# P08R6.net
KiCad netlist of a schematic drawn in EAGLE
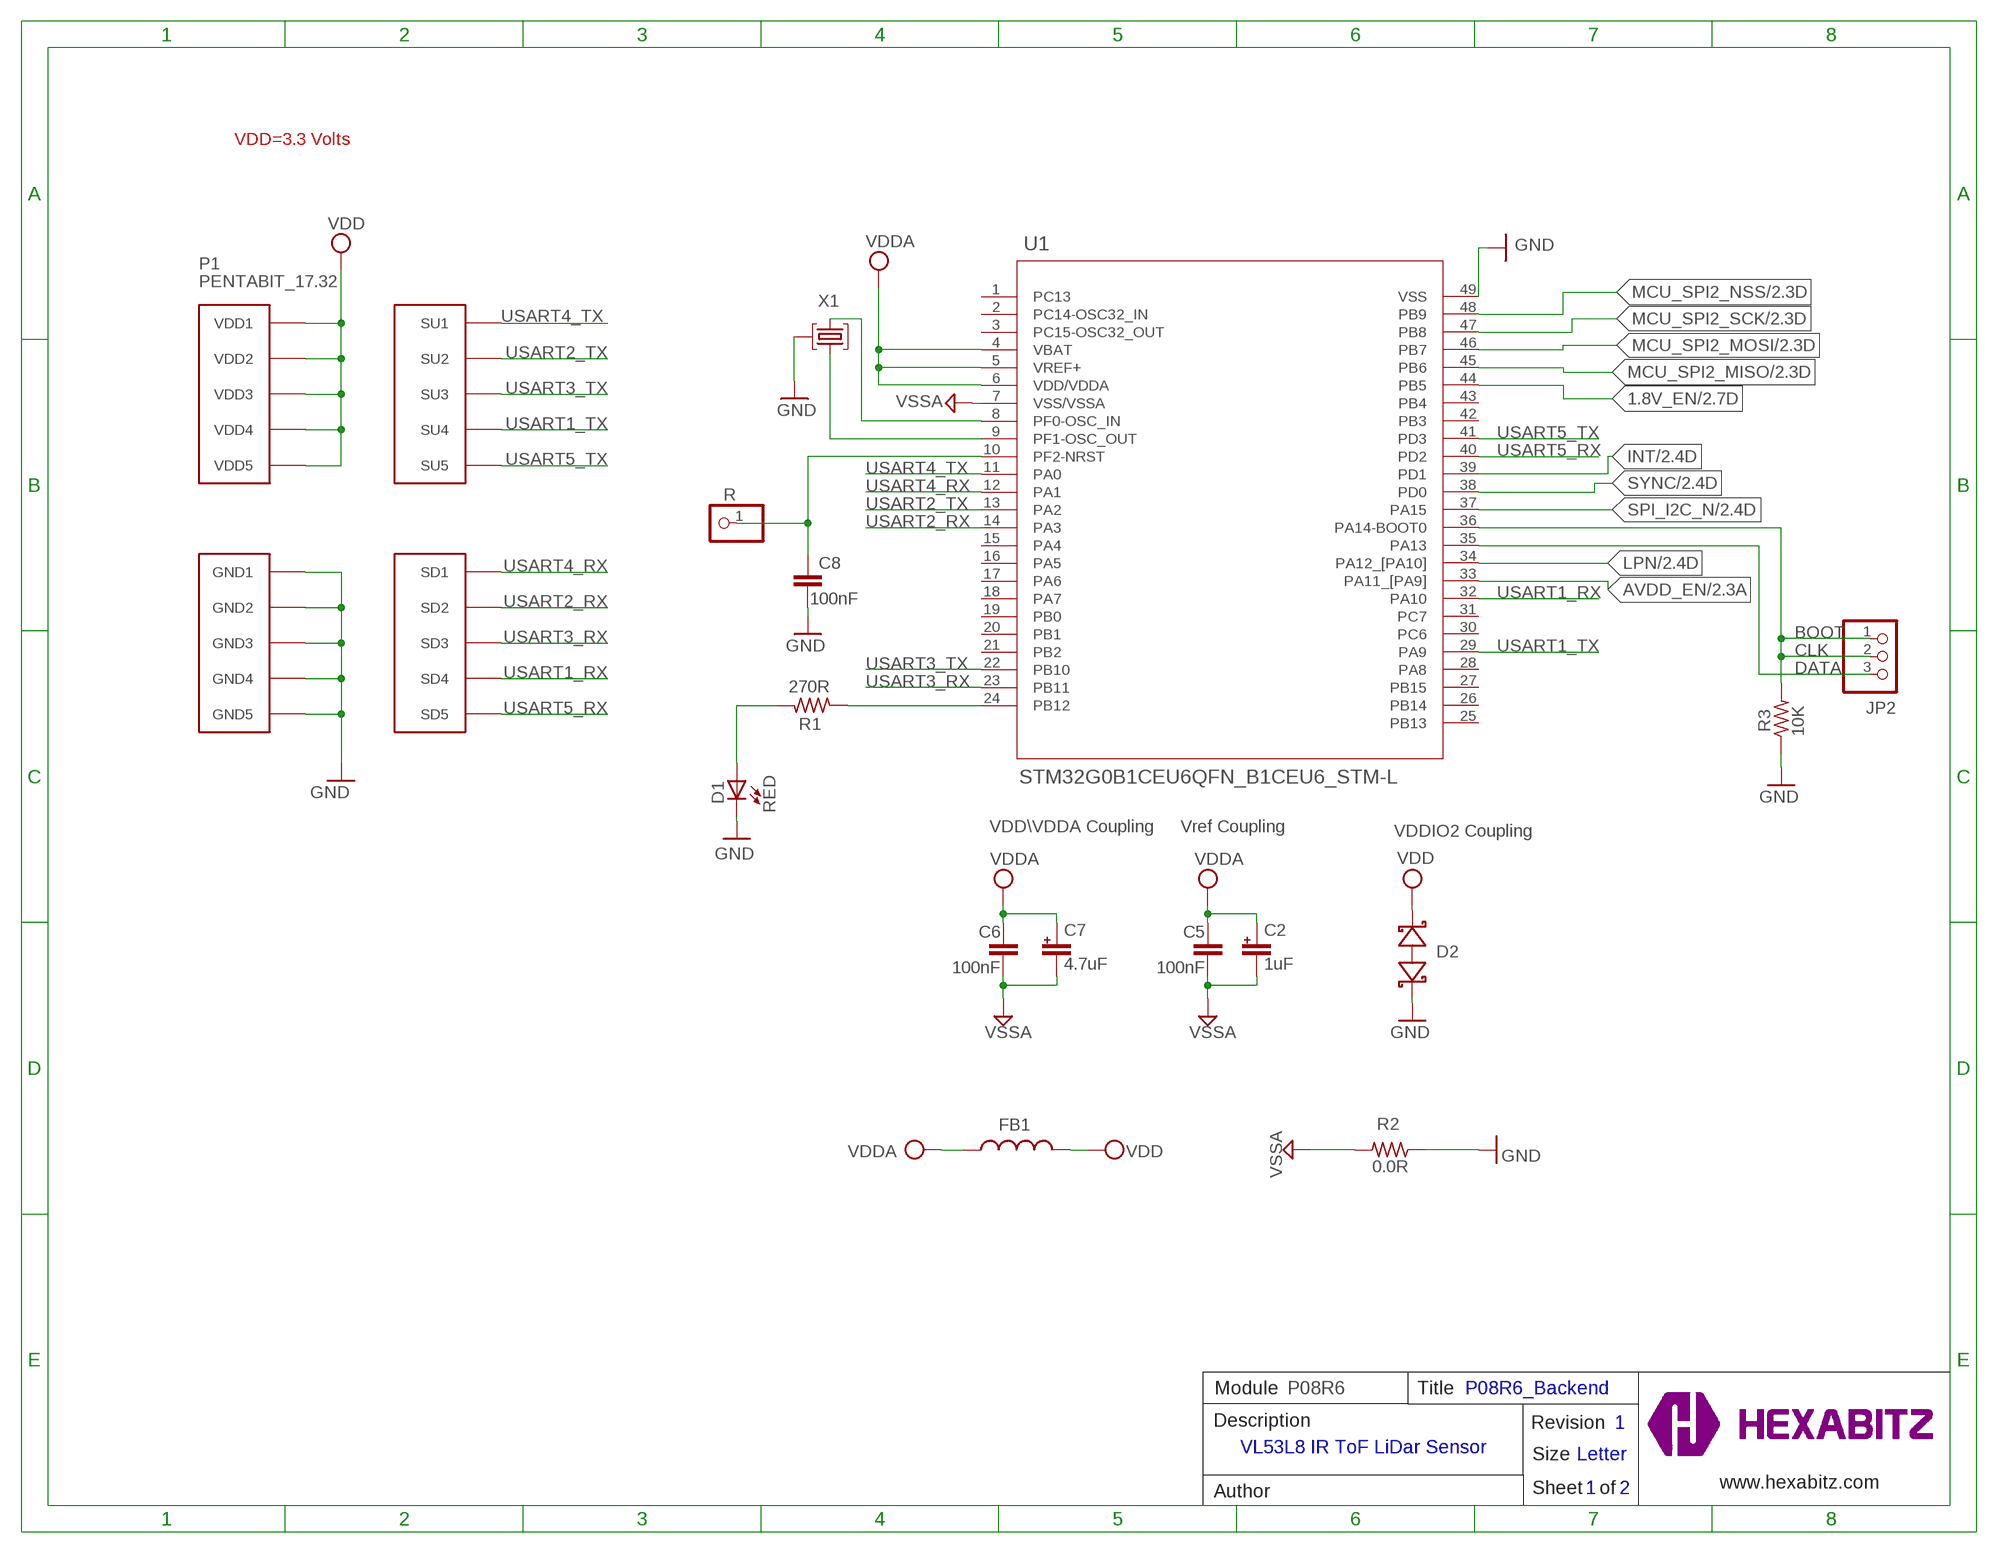
[diagram p0: schematic, sheet 1]
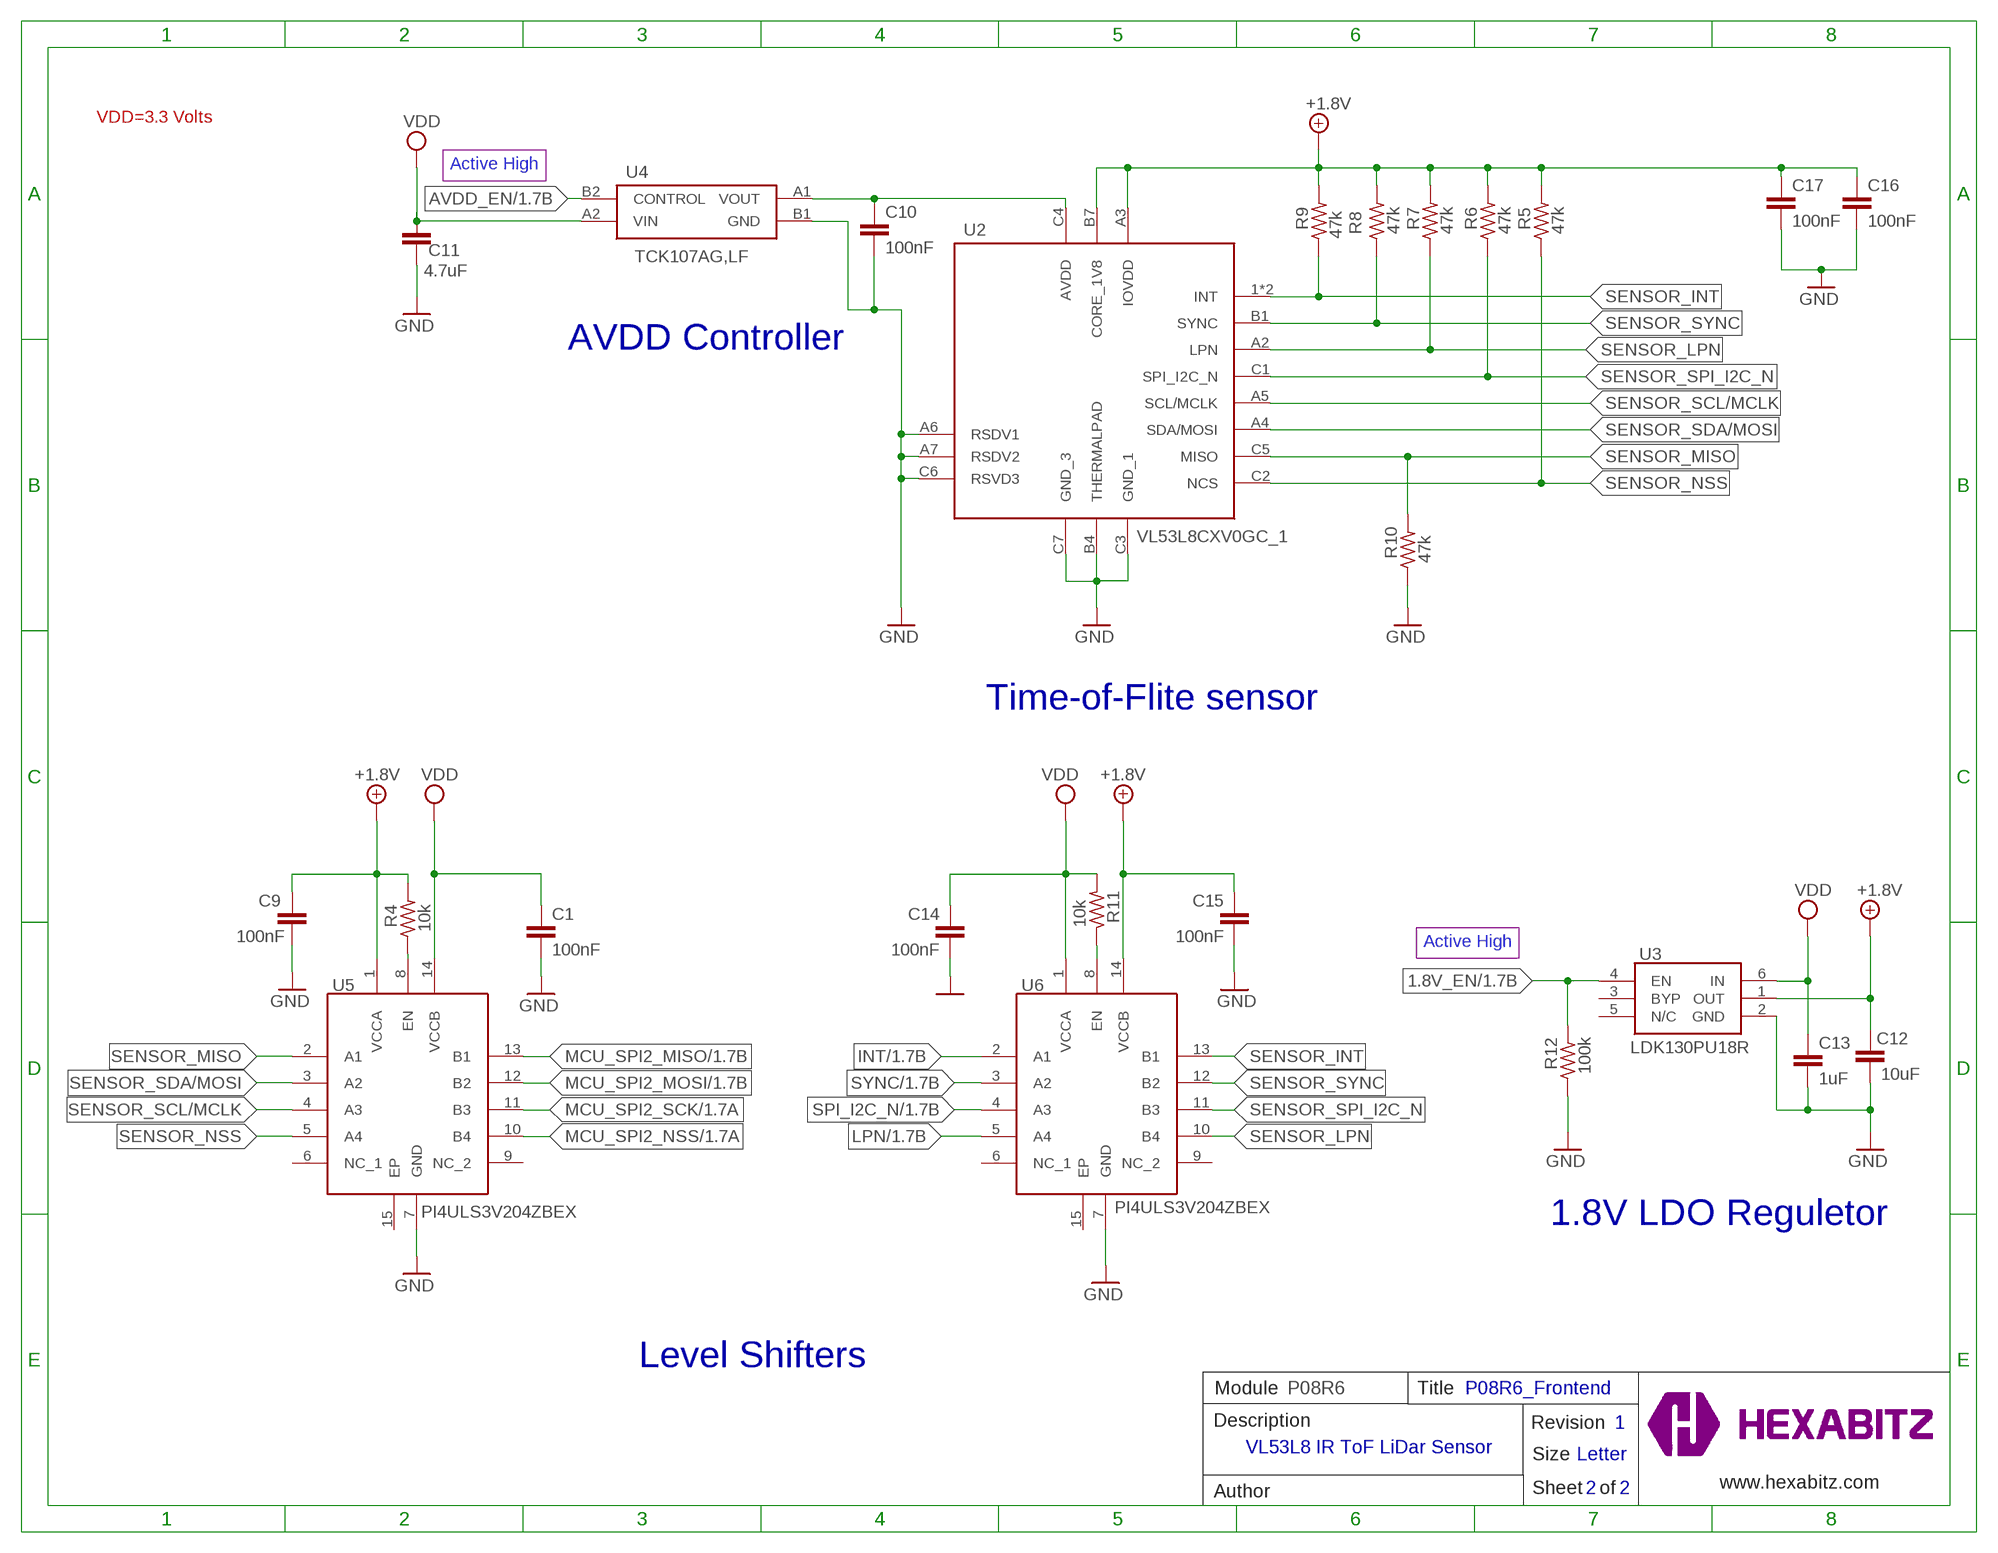
[diagram p1: schematic, sheet 2]

(export (version "E")
  (design (tool "Eeschema 10.0.6"))
  (components
    (comp (ref "C2")
      (value "1uF")
      (footprint "eagle-import:C-0603-POL")
      (libsource (lib "eagle-import") (part "C-0603-POL"))
    )
    (comp (ref "C5")
      (value "100nF")
      (footprint "eagle-import:C-0402")
      (libsource (lib "eagle-import") (part "C-0402"))
    )
    (comp (ref "C6")
      (value "100nF")
      (footprint "eagle-import:C-0402")
      (libsource (lib "eagle-import") (part "C-0402"))
    )
    (comp (ref "C7")
      (value "4.7uF")
      (footprint "eagle-import:C-0603-POL")
      (libsource (lib "eagle-import") (part "C-0603-POL"))
    )
    (comp (ref "C8")
      (value "100nF")
      (footprint "eagle-import:C-0402")
      (libsource (lib "eagle-import") (part "C-0402"))
    )
    (comp (ref "D1")
      (value "RED")
      (footprint "eagle-import:VLMS1300-GS08")
      (fields
        (field (name "MPN") "VLMS1300-GS08")
        (field (name "MFN") "Vishay")
        (field (name "MPN_1") "VLMS1300-GS08")
        (field (name "OCTOPART_URL") "https://octopart.com/vlms1300-gs08-vishay-21709201?r=sp&s=_gcP4_q8T1SC6PJQPTQ9yA")
      )
      (libsource (lib "eagle-import") (part "VLMS1300-GS08"))
    )
    (comp (ref "D2")
      (value "BOURNS_CDSOD323-T03SCBOURNS_CDSOD323-T03SC_0_0")
      (footprint "eagle-import:BOURNS_CDSOD323-T03SC_0")
      (fields (field (name "MPN") "CDSOD323-T03SC"))
      (libsource (lib "eagle-import") (part "BOURNS_CDSOD323-T03SCBOURNS_CDSOD323-T03SC_0_0"))
    )
    (comp (ref "FB1")
      (value "FB-TDK_MMZ1608Y300B")
      (footprint "eagle-import:FB-0603")
      (fields
        (field (name "MFN") "TDK ")
        (field (name "MPN") "MMZ1608Y300B")
        (field (name "OCTOPART_URL") "https://octopart.com/mmz1608y300b-tdk-368280?r=sp&s=cd9_2ZEqQ9q9UNBuQgHAiA")
      )
      (libsource (lib "eagle-import") (part "FB-0603"))
    )
    (comp (ref "JP2")
      (value "PINHD-1X3")
      (footprint "eagle-import:1X03")
      (libsource (lib "eagle-import") (part "PINHD-1X3"))
    )
    (comp (ref "P1")
      (value "PENTABIT_17.32")
      (footprint "eagle-import:PENTABIT_17.32")
      (libsource (lib "eagle-import") (part "PENTABIT_?17.32"))
    )
    (comp (ref "R")
      (value "R")
      (footprint "eagle-import:1X01")
      (fields (field (name "MPN") "87227-1"))
      (libsource (lib "eagle-import") (part "PINHD-1X1"))
    )
    (comp (ref "R1")
      (value "270R")
      (footprint "eagle-import:R-0402")
      (libsource (lib "eagle-import") (part "R-0402"))
    )
    (comp (ref "R2")
      (value "0.0R")
      (footprint "eagle-import:R-0402")
      (fields
        (field (name "MFN") "Yageo")
        (field (name "MPN") "RC0603JR-070RL")
        (field (name "OCTOPART_URL") "https://octopart.com/rc0603jr-070rl-yageo-1241539?r=sp&s=X2NteqRjRNWrnx42Y0aliA")
        (field (name "RESISTANCE") "0.0 Ohm")
      )
      (libsource (lib "eagle-import") (part "R-0402"))
    )
    (comp (ref "R3")
      (value "10K")
      (footprint "eagle-import:R-0402")
      (libsource (lib "eagle-import") (part "R-0402"))
    )
    (comp (ref "TRIMBLE-LOGO1")
      (value "HEXA-LOGO")
      (footprint "eagle-import:HEXA-LOGO")
      (libsource (lib "eagle-import") (part "HEXA-LOGO"))
    )
    (comp (ref "U1")
      (value "STM32G0B1CEU6QFN_B1CEU6_STM-L")
      (footprint "eagle-import:QFN_B1CEU6_STM-L")
      (fields
        (field (name "MANUFACTURER_PART_NUMBER") "STM32G0B1CEU6")
        (field (name "COPYRIGHT") "Copyright (C) 2021 Ultra Librarian. All rights reserved.")
      )
      (libsource (lib "eagle-import") (part "STM32G0B1CEU6QFN_B1CEU6_STM-L"))
    )
    (comp (ref "X1")
      (value "XTALL_CSTCE8M00G52")
      (footprint "eagle-import:XTALL_CSTCE8M00G52")
      (fields (field (name "MPN") "CSTCE8M00G52Z-R0"))
      (libsource (lib "eagle-import") (part "XTALL_CSTCE8M00G52"))
    )
    (comp (ref "C1")
      (value "100nF")
      (footprint "eagle-import:C-0402")
      (libsource (lib "eagle-import") (part "C-0402"))
    )
    (comp (ref "C9")
      (value "100nF")
      (footprint "eagle-import:C-0402")
      (libsource (lib "eagle-import") (part "C-0402"))
    )
    (comp (ref "C10")
      (value "100nF")
      (footprint "eagle-import:C-0402")
      (libsource (lib "eagle-import") (part "C-0402"))
    )
    (comp (ref "C11")
      (value "4.7uF")
      (footprint "eagle-import:C-0603")
      (libsource (lib "eagle-import") (part "C-0603"))
    )
    (comp (ref "C12")
      (value "10uF")
      (footprint "eagle-import:C-0402")
      (libsource (lib "eagle-import") (part "C-0402"))
    )
    (comp (ref "C13")
      (value "1uF")
      (footprint "eagle-import:C-0402")
      (libsource (lib "eagle-import") (part "C-0402"))
    )
    (comp (ref "C14")
      (value "100nF")
      (footprint "eagle-import:C-0402")
      (libsource (lib "eagle-import") (part "C-0402"))
    )
    (comp (ref "C15")
      (value "100nF")
      (footprint "eagle-import:C-0402")
      (libsource (lib "eagle-import") (part "C-0402"))
    )
    (comp (ref "C16")
      (value "100nF")
      (footprint "eagle-import:C-0402")
      (libsource (lib "eagle-import") (part "C-0402"))
    )
    (comp (ref "C17")
      (value "100nF")
      (footprint "eagle-import:C-0402")
      (libsource (lib "eagle-import") (part "C-0402"))
    )
    (comp (ref "R4")
      (value "10k")
      (footprint "eagle-import:R-0402")
      (libsource (lib "eagle-import") (part "R-0402"))
    )
    (comp (ref "R5")
      (value "47k")
      (footprint "eagle-import:R-0402")
      (libsource (lib "eagle-import") (part "R-0402"))
    )
    (comp (ref "R6")
      (value "47k")
      (footprint "eagle-import:R-0402")
      (libsource (lib "eagle-import") (part "R-0402"))
    )
    (comp (ref "R7")
      (value "47k")
      (footprint "eagle-import:R-0402")
      (libsource (lib "eagle-import") (part "R-0402"))
    )
    (comp (ref "R8")
      (value "47k")
      (footprint "eagle-import:R-0402")
      (libsource (lib "eagle-import") (part "R-0402"))
    )
    (comp (ref "R9")
      (value "47k")
      (footprint "eagle-import:R-0402")
      (libsource (lib "eagle-import") (part "R-0402"))
    )
    (comp (ref "R10")
      (value "47k")
      (footprint "eagle-import:R-0402")
      (libsource (lib "eagle-import") (part "R-0402"))
    )
    (comp (ref "R11")
      (value "10k")
      (footprint "eagle-import:R-0402")
      (libsource (lib "eagle-import") (part "R-0402"))
    )
    (comp (ref "R12")
      (value "100k")
      (footprint "eagle-import:R-0402")
      (libsource (lib "eagle-import") (part "R-0402"))
    )
    (comp (ref "U2")
      (value "VL53L8CXV0GC_1")
      (footprint "eagle-import:VL53L8CXV0GC1")
      (fields
        (field (name "ARROW_PART_NUMBER") "VL53L8CXV0GC/1")
        (field (name "MOUSER_PART_NUMBER") "511-VL53L8CXV0GC/1")
      )
      (libsource (lib "eagle-import") (part "VL53L8CXV0GC_1"))
    )
    (comp (ref "U3")
      (value "LDK130PU18R")
      (footprint "eagle-import:LDK130PU18R")
      (fields (field (name "MOUSER_PART_NUMBER") "511-LDK130PU18R"))
      (libsource (lib "eagle-import") (part "LDK130PU18R"))
    )
    (comp (ref "U4")
      (value "TCK107AG,LF")
      (footprint "eagle-import:BGA4C40P2X2_79X79X59")
      (fields (field (name "MOUSER_PART_NUMBER") "757-TCK107AGLF"))
      (libsource (lib "eagle-import") (part "TCK107AG,LF"))
    )
    (comp (ref "U5")
      (value "PI4ULS3V204ZBEX")
      (footprint "eagle-import:PI4ULS3V204ZBEX")
      (fields (field (name "MOUSER_PART_NUMBER") "729-PI4ULS3V204ZBEX"))
      (libsource (lib "eagle-import") (part "PI4ULS3V204ZBEX"))
    )
    (comp (ref "U6")
      (value "PI4ULS3V204ZBEX")
      (footprint "eagle-import:PI4ULS3V204ZBEX")
      (fields (field (name "MOUSER_PART_NUMBER") "729-PI4ULS3V204ZBEX"))
      (libsource (lib "eagle-import") (part "PI4ULS3V204ZBEX"))
    )
  )
  (nets
    (net (code "1") (name "+1.8V") (class "Default")
      (node (ref "C12") (pin "1") (pinfunction "1_1") (pintype "passive"))
      (node (ref "C15") (pin "1") (pinfunction "1_1") (pintype "passive"))
      (node (ref "C16") (pin "1") (pinfunction "1_1") (pintype "passive"))
      (node (ref "C17") (pin "1") (pinfunction "1_1") (pintype "passive"))
      (node (ref "C9") (pin "1") (pinfunction "1_1") (pintype "passive"))
      (node (ref "R4") (pin "2") (pinfunction "2_2") (pintype "passive"))
      (node (ref "R5") (pin "2") (pinfunction "2_2") (pintype "passive"))
      (node (ref "R6") (pin "2") (pinfunction "2_2") (pintype "passive"))
      (node (ref "R7") (pin "2") (pinfunction "2_2") (pintype "passive"))
      (node (ref "R8") (pin "2") (pinfunction "2_2") (pintype "passive"))
      (node (ref "R9") (pin "2") (pinfunction "2_2") (pintype "passive"))
      (node (ref "U2") (pin "A3") (pinfunction "IOVDD_A3") (pintype "bidirectional"))
      (node (ref "U2") (pin "B7") (pinfunction "CORE_1V8_B7") (pintype "bidirectional"))
      (node (ref "U3") (pin "1") (pinfunction "OUT_1") (pintype "bidirectional"))
      (node (ref "U5") (pin "1") (pinfunction "VCCA_1") (pintype "bidirectional"))
      (node (ref "U6") (pin "14") (pinfunction "VCCB_14") (pintype "bidirectional"))
    )
    (net (code "2") (name "1.8V_EN") (class "Default")
      (node (ref "R12") (pin "2") (pinfunction "2_2") (pintype "passive"))
      (node (ref "U1") (pin "44") (pinfunction "PB5_44") (pintype "bidirectional"))
      (node (ref "U3") (pin "4") (pinfunction "EN_4") (pintype "bidirectional"))
    )
    (net (code "3") (name "AVDD_EN") (class "Default")
      (node (ref "U1") (pin "33") (pinfunction "PA11_[PA9]_33") (pintype "bidirectional"))
      (node (ref "U4") (pin "B2") (pinfunction "CONTROL_B2") (pintype "bidirectional"))
    )
    (net (code "4") (name "CLK") (class "Default")
      (node (ref "JP2") (pin "1") (pinfunction "1_1") (pintype "passive"))
      (node (ref "JP2") (pin "2") (pinfunction "2_2") (pintype "passive"))
      (node (ref "R3") (pin "2") (pinfunction "2_2") (pintype "passive"))
      (node (ref "U1") (pin "36") (pinfunction "PA14-BOOT0_36") (pintype "bidirectional"))
    )
    (net (code "5") (name "DATA") (class "Default")
      (node (ref "JP2") (pin "3") (pinfunction "3_3") (pintype "passive"))
      (node (ref "U1") (pin "35") (pinfunction "PA13_35") (pintype "bidirectional"))
    )
    (net (code "6") (name "GND") (class "Default")
      (node (ref "C1") (pin "2") (pinfunction "2_2") (pintype "passive"))
      (node (ref "C10") (pin "2") (pinfunction "2_2") (pintype "passive"))
      (node (ref "C11") (pin "2") (pinfunction "2_2") (pintype "passive"))
      (node (ref "C12") (pin "2") (pinfunction "2_2") (pintype "passive"))
      (node (ref "C13") (pin "2") (pinfunction "2_2") (pintype "passive"))
      (node (ref "C14") (pin "2") (pinfunction "2_2") (pintype "passive"))
      (node (ref "C15") (pin "2") (pinfunction "2_2") (pintype "passive"))
      (node (ref "C16") (pin "2") (pinfunction "2_2") (pintype "passive"))
      (node (ref "C17") (pin "2") (pinfunction "2_2") (pintype "passive"))
      (node (ref "C8") (pin "2") (pinfunction "2_2") (pintype "passive"))
      (node (ref "C9") (pin "2") (pinfunction "2_2") (pintype "passive"))
      (node (ref "D1") (pin "C") (pinfunction "C_C") (pintype "passive"))
      (node (ref "D2") (pin "2") (pinfunction "C_2") (pintype "passive"))
      (node (ref "P1") (pin "PAD_PD10") (pinfunction "GND5_PAD_PD10") (pintype "power_in"))
      (node (ref "P1") (pin "PAD_PD6") (pinfunction "GND1_PAD_PD6") (pintype "power_in"))
      (node (ref "P1") (pin "PAD_PD7") (pinfunction "GND2_PAD_PD7") (pintype "power_in"))
      (node (ref "P1") (pin "PAD_PD8") (pinfunction "GND3_PAD_PD8") (pintype "power_in"))
      (node (ref "P1") (pin "PAD_PD9") (pinfunction "GND4_PAD_PD9") (pintype "power_in"))
      (node (ref "R10") (pin "1") (pinfunction "1_1") (pintype "passive"))
      (node (ref "R12") (pin "1") (pinfunction "1_1") (pintype "passive"))
      (node (ref "R2") (pin "1") (pinfunction "1_1") (pintype "passive"))
      (node (ref "R3") (pin "1") (pinfunction "1_1") (pintype "passive"))
      (node (ref "U1") (pin "49") (pinfunction "VSS_49") (pintype "passive"))
      (node (ref "U2") (pin "A6") (pinfunction "RSDV1_A6") (pintype "bidirectional"))
      (node (ref "U2") (pin "A7") (pinfunction "RSDV2_A7") (pintype "bidirectional"))
      (node (ref "U2") (pin "B4") (pinfunction "THERMALPAD_B4") (pintype "bidirectional"))
      (node (ref "U2") (pin "C3") (pinfunction "GND_1_C3") (pintype "bidirectional"))
      (node (ref "U2") (pin "C6") (pinfunction "RSVD3_C6") (pintype "bidirectional"))
      (node (ref "U2") (pin "C7") (pinfunction "GND_3_C7") (pintype "bidirectional"))
      (node (ref "U3") (pin "2") (pinfunction "GND_2") (pintype "bidirectional"))
      (node (ref "U4") (pin "B1") (pinfunction "GND_B1") (pintype "bidirectional"))
      (node (ref "U5") (pin "7") (pinfunction "GND_7") (pintype "bidirectional"))
      (node (ref "U6") (pin "7") (pinfunction "GND_7") (pintype "bidirectional"))
      (node (ref "X1") (pin "P$2") (pinfunction "2_P$2") (pintype "passive"))
    )
    (net (code "7") (name "INT") (class "Default")
      (node (ref "U1") (pin "39") (pinfunction "PD1_39") (pintype "bidirectional"))
      (node (ref "U6") (pin "2") (pinfunction "A1_2") (pintype "bidirectional"))
    )
    (net (code "8") (name "LPN") (class "Default")
      (node (ref "U1") (pin "34") (pinfunction "PA12_[PA10]_34") (pintype "bidirectional"))
      (node (ref "U6") (pin "5") (pinfunction "A4_5") (pintype "bidirectional"))
    )
    (net (code "9") (name "MCU_SPI2_MISO") (class "Default")
      (node (ref "U1") (pin "45") (pinfunction "PB6_45") (pintype "bidirectional"))
      (node (ref "U5") (pin "13") (pinfunction "B1_13") (pintype "bidirectional"))
    )
    (net (code "10") (name "MCU_SPI2_MOSI") (class "Default")
      (node (ref "U1") (pin "46") (pinfunction "PB7_46") (pintype "bidirectional"))
      (node (ref "U5") (pin "12") (pinfunction "B2_12") (pintype "bidirectional"))
    )
    (net (code "11") (name "MCU_SPI2_NSS") (class "Default")
      (node (ref "U1") (pin "48") (pinfunction "PB9_48") (pintype "bidirectional"))
      (node (ref "U5") (pin "10") (pinfunction "B4_10") (pintype "bidirectional"))
    )
    (net (code "12") (name "MCU_SPI2_SCK") (class "Default")
      (node (ref "U1") (pin "47") (pinfunction "PB8_47") (pintype "bidirectional"))
      (node (ref "U5") (pin "11") (pinfunction "B3_11") (pintype "bidirectional"))
    )
    (net (code "13") (name "Net-(D1-PadA)") (class "Default")
      (node (ref "D1") (pin "A") (pinfunction "A_A") (pintype "passive"))
      (node (ref "R1") (pin "2") (pinfunction "2_2") (pintype "passive"))
    )
    (net (code "14") (name "Net-(U1-PB12)") (class "Default")
      (node (ref "R1") (pin "1") (pinfunction "1_1") (pintype "passive"))
      (node (ref "U1") (pin "24") (pinfunction "PB12_24") (pintype "bidirectional"))
    )
    (net (code "15") (name "Net-(U1-PF0-OSC_IN)") (class "Default")
      (node (ref "U1") (pin "8") (pinfunction "PF0-OSC_IN_8") (pintype "bidirectional"))
      (node (ref "X1") (pin "P$3") (pinfunction "3_P$3") (pintype "passive"))
    )
    (net (code "16") (name "Net-(U1-PF1-OSC_OUT)") (class "Default")
      (node (ref "U1") (pin "9") (pinfunction "PF1-OSC_OUT_9") (pintype "output"))
      (node (ref "X1") (pin "P$1") (pinfunction "1_P$1") (pintype "passive"))
    )
    (net (code "17") (name "Net-(U1-PF2-NRST)") (class "Default")
      (node (ref "C8") (pin "1") (pinfunction "1_1") (pintype "passive"))
      (node (ref "R") (pin "1") (pinfunction "1_1") (pintype "passive"))
      (node (ref "U1") (pin "10") (pinfunction "PF2-NRST_10") (pintype "bidirectional"))
    )
    (net (code "18") (name "Net-(U2-AVDD)") (class "Default")
      (node (ref "C10") (pin "1") (pinfunction "1_1") (pintype "passive"))
      (node (ref "U2") (pin "C4") (pinfunction "AVDD_C4") (pintype "bidirectional"))
      (node (ref "U4") (pin "A1") (pinfunction "VOUT_A1") (pintype "bidirectional"))
    )
    (net (code "19") (name "Net-(U5-EN)") (class "Default")
      (node (ref "R4") (pin "1") (pinfunction "1_1") (pintype "passive"))
      (node (ref "U5") (pin "8") (pinfunction "EN_8") (pintype "bidirectional"))
    )
    (net (code "20") (name "Net-(U6-EN)") (class "Default")
      (node (ref "R11") (pin "1") (pinfunction "1_1") (pintype "passive"))
      (node (ref "U6") (pin "8") (pinfunction "EN_8") (pintype "bidirectional"))
    )
    (net (code "21") (name "SENSOR_INT") (class "Default")
      (node (ref "R9") (pin "1") (pinfunction "1_1") (pintype "passive"))
      (node (ref "U2") (pin "1") (pinfunction "INT_1") (pintype "bidirectional"))
      (node (ref "U2") (pin "A1") (pinfunction "INT_A1") (pintype "bidirectional"))
      (node (ref "U6") (pin "13") (pinfunction "B1_13") (pintype "bidirectional"))
    )
    (net (code "22") (name "SENSOR_LPN") (class "Default")
      (node (ref "R7") (pin "1") (pinfunction "1_1") (pintype "passive"))
      (node (ref "U2") (pin "A2") (pinfunction "LPN_A2") (pintype "bidirectional"))
      (node (ref "U6") (pin "10") (pinfunction "B4_10") (pintype "bidirectional"))
    )
    (net (code "23") (name "SENSOR_MISO") (class "Default")
      (node (ref "R10") (pin "2") (pinfunction "2_2") (pintype "passive"))
      (node (ref "U2") (pin "C5") (pinfunction "MISO_C5") (pintype "bidirectional"))
      (node (ref "U5") (pin "2") (pinfunction "A1_2") (pintype "bidirectional"))
    )
    (net (code "24") (name "SENSOR_NSS") (class "Default")
      (node (ref "R5") (pin "1") (pinfunction "1_1") (pintype "passive"))
      (node (ref "U2") (pin "C2") (pinfunction "NCS_C2") (pintype "bidirectional"))
      (node (ref "U5") (pin "5") (pinfunction "A4_5") (pintype "bidirectional"))
    )
    (net (code "25") (name "SENSOR_SCL{slash}MCLK") (class "Default")
      (node (ref "U2") (pin "A5") (pinfunction "SCL/MCLK_A5") (pintype "bidirectional"))
      (node (ref "U5") (pin "4") (pinfunction "A3_4") (pintype "bidirectional"))
    )
    (net (code "26") (name "SENSOR_SDA{slash}MOSI") (class "Default")
      (node (ref "U2") (pin "A4") (pinfunction "SDA/MOSI_A4") (pintype "bidirectional"))
      (node (ref "U5") (pin "3") (pinfunction "A2_3") (pintype "bidirectional"))
    )
    (net (code "27") (name "SENSOR_SPI_I2C_N") (class "Default")
      (node (ref "R6") (pin "1") (pinfunction "1_1") (pintype "passive"))
      (node (ref "U2") (pin "C1") (pinfunction "SPI_I2C_N_C1") (pintype "bidirectional"))
      (node (ref "U6") (pin "11") (pinfunction "B3_11") (pintype "bidirectional"))
    )
    (net (code "28") (name "SENSOR_SYNC") (class "Default")
      (node (ref "R8") (pin "1") (pinfunction "1_1") (pintype "passive"))
      (node (ref "U2") (pin "B1") (pinfunction "SYNC_B1") (pintype "bidirectional"))
      (node (ref "U6") (pin "12") (pinfunction "B2_12") (pintype "bidirectional"))
    )
    (net (code "29") (name "SPI_I2C_N") (class "Default")
      (node (ref "U1") (pin "37") (pinfunction "PA15_37") (pintype "bidirectional"))
      (node (ref "U6") (pin "4") (pinfunction "A3_4") (pintype "bidirectional"))
    )
    (net (code "30") (name "SYNC") (class "Default")
      (node (ref "U1") (pin "38") (pinfunction "PD0_38") (pintype "bidirectional"))
      (node (ref "U6") (pin "3") (pinfunction "A2_3") (pintype "bidirectional"))
    )
    (net (code "31") (name "USART1_RX") (class "Default")
      (node (ref "P1") (pin "PAD_PD4") (pinfunction "SD4_PAD_PD4") (pintype "bidirectional"))
      (node (ref "U1") (pin "32") (pinfunction "PA10_32") (pintype "bidirectional"))
    )
    (net (code "32") (name "USART1_TX") (class "Default")
      (node (ref "P1") (pin "PAD_PU4") (pinfunction "SU4_PAD_PU4") (pintype "bidirectional"))
      (node (ref "U1") (pin "29") (pinfunction "PA9_29") (pintype "bidirectional"))
    )
    (net (code "33") (name "USART2_RX") (class "Default")
      (node (ref "P1") (pin "PAD_PD2") (pinfunction "SD2_PAD_PD2") (pintype "bidirectional"))
      (node (ref "U1") (pin "14") (pinfunction "PA3_14") (pintype "bidirectional"))
    )
    (net (code "34") (name "USART2_TX") (class "Default")
      (node (ref "P1") (pin "PAD_PU2") (pinfunction "SU2_PAD_PU2") (pintype "bidirectional"))
      (node (ref "U1") (pin "13") (pinfunction "PA2_13") (pintype "bidirectional"))
    )
    (net (code "35") (name "USART3_RX") (class "Default")
      (node (ref "P1") (pin "PAD_PD3") (pinfunction "SD3_PAD_PD3") (pintype "bidirectional"))
      (node (ref "U1") (pin "23") (pinfunction "PB11_23") (pintype "bidirectional"))
    )
    (net (code "36") (name "USART3_TX") (class "Default")
      (node (ref "P1") (pin "PAD_PU3") (pinfunction "SU3_PAD_PU3") (pintype "bidirectional"))
      (node (ref "U1") (pin "22") (pinfunction "PB10_22") (pintype "bidirectional"))
    )
    (net (code "37") (name "USART4_RX") (class "Default")
      (node (ref "P1") (pin "PAD_PD1") (pinfunction "SD1_PAD_PD1") (pintype "bidirectional"))
      (node (ref "U1") (pin "12") (pinfunction "PA1_12") (pintype "bidirectional"))
    )
    (net (code "38") (name "USART4_TX") (class "Default")
      (node (ref "P1") (pin "PAD_PU1") (pinfunction "SU1_PAD_PU1") (pintype "bidirectional"))
      (node (ref "U1") (pin "11") (pinfunction "PA0_11") (pintype "bidirectional"))
    )
    (net (code "39") (name "USART5_RX") (class "Default")
      (node (ref "P1") (pin "PAD_PD5") (pinfunction "SD5_PAD_PD5") (pintype "bidirectional"))
      (node (ref "U1") (pin "40") (pinfunction "PD2_40") (pintype "bidirectional"))
    )
    (net (code "40") (name "USART5_TX") (class "Default")
      (node (ref "P1") (pin "PAD_PU5") (pinfunction "SU5_PAD_PU5") (pintype "bidirectional"))
      (node (ref "U1") (pin "41") (pinfunction "PD3_41") (pintype "bidirectional"))
    )
    (net (code "41") (name "VDD") (class "Default")
      (node (ref "C1") (pin "1") (pinfunction "1_1") (pintype "passive"))
      (node (ref "C11") (pin "1") (pinfunction "1_1") (pintype "passive"))
      (node (ref "C13") (pin "1") (pinfunction "1_1") (pintype "passive"))
      (node (ref "C14") (pin "1") (pinfunction "1_1") (pintype "passive"))
      (node (ref "D2") (pin "1") (pinfunction "A_1") (pintype "passive"))
      (node (ref "FB1") (pin "2") (pinfunction "2_2") (pintype "passive"))
      (node (ref "P1") (pin "PAD_PU10") (pinfunction "VDD5_PAD_PU10") (pintype "power_in"))
      (node (ref "P1") (pin "PAD_PU6") (pinfunction "VDD1_PAD_PU6") (pintype "power_in"))
      (node (ref "P1") (pin "PAD_PU7") (pinfunction "VDD2_PAD_PU7") (pintype "power_in"))
      (node (ref "P1") (pin "PAD_PU8") (pinfunction "VDD3_PAD_PU8") (pintype "power_in"))
      (node (ref "P1") (pin "PAD_PU9") (pinfunction "VDD4_PAD_PU9") (pintype "power_in"))
      (node (ref "R11") (pin "2") (pinfunction "2_2") (pintype "passive"))
      (node (ref "U3") (pin "6") (pinfunction "IN_6") (pintype "bidirectional"))
      (node (ref "U4") (pin "A2") (pinfunction "VIN_A2") (pintype "bidirectional"))
      (node (ref "U5") (pin "14") (pinfunction "VCCB_14") (pintype "bidirectional"))
      (node (ref "U6") (pin "1") (pinfunction "VCCA_1") (pintype "bidirectional"))
    )
    (net (code "42") (name "VDDA") (class "Default")
      (node (ref "C2") (pin "1") (pinfunction "1_1") (pintype "passive"))
      (node (ref "C5") (pin "1") (pinfunction "1_1") (pintype "passive"))
      (node (ref "C6") (pin "1") (pinfunction "1_1") (pintype "passive"))
      (node (ref "C7") (pin "1") (pinfunction "1_1") (pintype "passive"))
      (node (ref "FB1") (pin "1") (pinfunction "1_1") (pintype "passive"))
      (node (ref "U1") (pin "4") (pinfunction "VBAT_4") (pintype "passive"))
      (node (ref "U1") (pin "5") (pinfunction "VREF+_5") (pintype "power_in"))
      (node (ref "U1") (pin "6") (pinfunction "VDD/VDDA_6") (pintype "power_in"))
    )
    (net (code "43") (name "VSSA") (class "Default")
      (node (ref "C2") (pin "2") (pinfunction "2_2") (pintype "passive"))
      (node (ref "C5") (pin "2") (pinfunction "2_2") (pintype "passive"))
      (node (ref "C6") (pin "2") (pinfunction "2_2") (pintype "passive"))
      (node (ref "C7") (pin "2") (pinfunction "2_2") (pintype "passive"))
      (node (ref "R2") (pin "2") (pinfunction "2_2") (pintype "passive"))
      (node (ref "U1") (pin "7") (pinfunction "VSS/VSSA_7") (pintype "passive"))
    )
    (net (code "44") (name "unconnected-(U1-PA4-Pad15)") (class "Default")
      (node (ref "U1") (pin "15") (pinfunction "PA4_15") (pintype "bidirectional"))
    )
    (net (code "45") (name "unconnected-(U1-PA5-Pad16)") (class "Default")
      (node (ref "U1") (pin "16") (pinfunction "PA5_16") (pintype "bidirectional"))
    )
    (net (code "46") (name "unconnected-(U1-PA6-Pad17)") (class "Default")
      (node (ref "U1") (pin "17") (pinfunction "PA6_17") (pintype "bidirectional"))
    )
    (net (code "47") (name "unconnected-(U1-PA7-Pad18)") (class "Default")
      (node (ref "U1") (pin "18") (pinfunction "PA7_18") (pintype "bidirectional"))
    )
    (net (code "48") (name "unconnected-(U1-PA8-Pad28)") (class "Default")
      (node (ref "U1") (pin "28") (pinfunction "PA8_28") (pintype "bidirectional"))
    )
    (net (code "49") (name "unconnected-(U1-PB0-Pad19)") (class "Default")
      (node (ref "U1") (pin "19") (pinfunction "PB0_19") (pintype "bidirectional"))
    )
    (net (code "50") (name "unconnected-(U1-PB1-Pad20)") (class "Default")
      (node (ref "U1") (pin "20") (pinfunction "PB1_20") (pintype "bidirectional"))
    )
    (net (code "51") (name "unconnected-(U1-PB2-Pad21)") (class "Default")
      (node (ref "U1") (pin "21") (pinfunction "PB2_21") (pintype "bidirectional"))
    )
    (net (code "52") (name "unconnected-(U1-PB3-Pad42)") (class "Default")
      (node (ref "U1") (pin "42") (pinfunction "PB3_42") (pintype "bidirectional"))
    )
    (net (code "53") (name "unconnected-(U1-PB4-Pad43)") (class "Default")
      (node (ref "U1") (pin "43") (pinfunction "PB4_43") (pintype "bidirectional"))
    )
    (net (code "54") (name "unconnected-(U1-PB13-Pad25)") (class "Default")
      (node (ref "U1") (pin "25") (pinfunction "PB13_25") (pintype "bidirectional"))
    )
    (net (code "55") (name "unconnected-(U1-PB14-Pad26)") (class "Default")
      (node (ref "U1") (pin "26") (pinfunction "PB14_26") (pintype "bidirectional"))
    )
    (net (code "56") (name "unconnected-(U1-PB15-Pad27)") (class "Default")
      (node (ref "U1") (pin "27") (pinfunction "PB15_27") (pintype "bidirectional"))
    )
    (net (code "57") (name "unconnected-(U1-PC6-Pad30)") (class "Default")
      (node (ref "U1") (pin "30") (pinfunction "PC6_30") (pintype "bidirectional"))
    )
    (net (code "58") (name "unconnected-(U1-PC7-Pad31)") (class "Default")
      (node (ref "U1") (pin "31") (pinfunction "PC7_31") (pintype "bidirectional"))
    )
    (net (code "59") (name "unconnected-(U1-PC13-Pad1)") (class "Default")
      (node (ref "U1") (pin "1") (pinfunction "PC13_1") (pintype "bidirectional"))
    )
    (net (code "60") (name "unconnected-(U1-PC14-OSC32_IN-Pad2)") (class "Default")
      (node (ref "U1") (pin "2") (pinfunction "PC14-OSC32_IN_2") (pintype "bidirectional"))
    )
    (net (code "61") (name "unconnected-(U1-PC15-OSC32_OUT-Pad3)") (class "Default")
      (node (ref "U1") (pin "3") (pinfunction "PC15-OSC32_OUT_3") (pintype "output"))
    )
    (net (code "62") (name "unconnected-(U3-BYP-Pad3)") (class "Default")
      (node (ref "U3") (pin "3") (pinfunction "BYP_3") (pintype "no_connect"))
    )
    (net (code "63") (name "unconnected-(U3-N{slash}C-Pad5)") (class "Default")
      (node (ref "U3") (pin "5") (pinfunction "N/C_5") (pintype "no_connect"))
    )
    (net (code "64") (name "unconnected-(U5-EP-Pad15)") (class "Default")
      (node (ref "U5") (pin "15") (pinfunction "EP_15") (pintype "no_connect"))
    )
    (net (code "65") (name "unconnected-(U5-NC_1-Pad6)") (class "Default")
      (node (ref "U5") (pin "6") (pinfunction "NC_1_6") (pintype "no_connect"))
    )
    (net (code "66") (name "unconnected-(U5-NC_2-Pad9)") (class "Default")
      (node (ref "U5") (pin "9") (pinfunction "NC_2_9") (pintype "no_connect"))
    )
    (net (code "67") (name "unconnected-(U6-EP-Pad15)") (class "Default")
      (node (ref "U6") (pin "15") (pinfunction "EP_15") (pintype "no_connect"))
    )
    (net (code "68") (name "unconnected-(U6-NC_1-Pad6)") (class "Default")
      (node (ref "U6") (pin "6") (pinfunction "NC_1_6") (pintype "no_connect"))
    )
    (net (code "69") (name "unconnected-(U6-NC_2-Pad9)") (class "Default")
      (node (ref "U6") (pin "9") (pinfunction "NC_2_9") (pintype "no_connect"))
    )
  )
)
